# Audio.net
KiCad netlist of a schematic drawn in Altium Designer
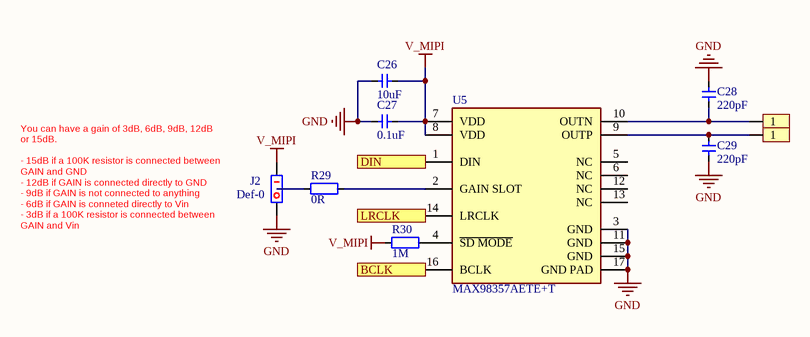
[diagram p0: Audio.SchDoc]

(export (version "E")
  (design (tool "Eeschema 10.0.6"))
  (components
    (comp (ref "*1") (value "SPEAKER") (footprint "SPEAKER") (libsource (lib "MyPcbLib") (part "SPEAKER")))
    (comp (ref "*2") (value "SPEAKER") (footprint "SPEAKER") (libsource (lib "MyPcbLib") (part "SPEAKER")))
    (comp (ref "C26")
      (value "10uF")
      (footprint "CAP_0402")
      (description "Capacitor")
      (libsource (lib "MyPcbLib") (part "电容-0402"))
    )
    (comp (ref "C27")
      (value "0.1uF")
      (footprint "CAP_0402")
      (description "Capacitor")
      (libsource (lib "MyPcbLib") (part "电容-0402"))
    )
    (comp (ref "C28")
      (value "220pF")
      (footprint "CAP_0402")
      (description "Capacitor")
      (libsource (lib "MyPcbLib") (part "电容-0402"))
    )
    (comp (ref "C29")
      (value "220pF")
      (footprint "CAP_0402")
      (description "Capacitor")
      (libsource (lib "MyPcbLib") (part "电容-0402"))
    )
    (comp (ref "J2")
      (value "Def-0")
      (footprint "jumper-3")
      (description "Resistor")
      (fields (field (name "PUBLISHER") "Altium Limited"))
      (libsource (lib "MyPcbLib") (part "选择跳线"))
    )
    (comp (ref "R29")
      (value "0R")
      (footprint "RES_0402")
      (description "Resistor")
      (libsource (lib "MyPcbLib") (part "电阻-0402"))
    )
    (comp (ref "R30")
      (value "1M")
      (footprint "RES_0402")
      (description "Resistor")
      (libsource (lib "MiniDisplay") (part "电阻-0402"))
    )
    (comp (ref "U5")
      (value "MAX98357AETE")
      (footprint "TQFN-16")
      (description "IC Amplifier IC 2-Channel (Stereo) Class D 16-TQFN (3x3)")
      (fields
        (field (name "MANUFACTURER") "Maxim Electronics")
        (field (name "MOUSER PART NUMBER") "700-MAX98357AETE+T")
        (field (name "PART NUMBER") "MAX98357AETE+T")
      )
      (libsource (lib "MiniDisplay") (part "MAX98357AETE"))
    )
  )
  (nets
    (net (code "1") (name "/BCLK") (class "Default")
      (node (ref "U5") (pin "16") (pinfunction "BCLK_16") (pintype "passive"))
    )
    (net (code "2") (name "/DIN") (class "Default")
      (node (ref "U5") (pin "1") (pinfunction "DIN_1") (pintype "passive"))
    )
    (net (code "3") (name "/LRCLK") (class "Default")
      (node (ref "U5") (pin "14") (pinfunction "LRCLK_14") (pintype "passive"))
    )
    (net (code "4") (name "GND") (class "Default")
      (node (ref "C26") (pin "1") (pinfunction "1_1") (pintype "passive"))
      (node (ref "C27") (pin "1") (pinfunction "1_1") (pintype "passive"))
      (node (ref "C28") (pin "2") (pinfunction "2_2") (pintype "passive"))
      (node (ref "C29") (pin "2") (pinfunction "2_2") (pintype "passive"))
      (node (ref "J2") (pin "1") (pinfunction "1_1") (pintype "passive"))
      (node (ref "U5") (pin "11") (pinfunction "GND_11") (pintype "passive"))
      (node (ref "U5") (pin "15") (pinfunction "GND_15") (pintype "passive"))
      (node (ref "U5") (pin "17") (pinfunction "GND_PAD_17") (pintype "passive"))
      (node (ref "U5") (pin "3") (pinfunction "GND_3") (pintype "passive"))
    )
    (net (code "5") (name "Net-(J2-Pad2)") (class "Default")
      (node (ref "J2") (pin "2") (pinfunction "2_2") (pintype "passive"))
      (node (ref "R29") (pin "1") (pinfunction "1_1") (pintype "passive"))
    )
    (net (code "6") (name "Net-(U5-GAIN_SLOT)") (class "Default")
      (node (ref "R29") (pin "2") (pinfunction "2_2") (pintype "passive"))
      (node (ref "U5") (pin "2") (pinfunction "GAIN_SLOT_2") (pintype "passive"))
    )
    (net (code "7") (name "Net-(U5-OUTN)") (class "Default")
      (node (ref "*1") (pin "1") (pinfunction "1_1") (pintype "passive"))
      (node (ref "C28") (pin "1") (pinfunction "1_1") (pintype "passive"))
      (node (ref "U5") (pin "10") (pinfunction "OUTN_10") (pintype "passive"))
    )
    (net (code "8") (name "Net-(U5-OUTP)") (class "Default")
      (node (ref "*2") (pin "1") (pinfunction "1_1") (pintype "passive"))
      (node (ref "C29") (pin "1") (pinfunction "1_1") (pintype "passive"))
      (node (ref "U5") (pin "9") (pinfunction "OUTP_9") (pintype "passive"))
    )
    (net (code "9") (name "Net-(U5-~{SD_MODE})") (class "Default")
      (node (ref "R30") (pin "2") (pinfunction "2_2") (pintype "passive"))
      (node (ref "U5") (pin "4") (pinfunction "~{SD_MODE}_4") (pintype "passive"))
    )
    (net (code "10") (name "V_MIPI") (class "Default")
      (node (ref "C26") (pin "2") (pinfunction "2_2") (pintype "passive"))
      (node (ref "C27") (pin "2") (pinfunction "2_2") (pintype "passive"))
      (node (ref "J2") (pin "3") (pinfunction "3_3") (pintype "passive"))
      (node (ref "R30") (pin "1") (pinfunction "1_1") (pintype "passive"))
      (node (ref "U5") (pin "7") (pinfunction "VDD_7") (pintype "passive"))
      (node (ref "U5") (pin "8") (pinfunction "VDD_8") (pintype "passive"))
    )
    (net (code "11") (name "unconnected-(U5-NC-Pad5)") (class "Default")
      (node (ref "U5") (pin "5") (pinfunction "NC_5") (pintype "passive"))
    )
    (net (code "12") (name "unconnected-(U5-NC-Pad6)") (class "Default")
      (node (ref "U5") (pin "6") (pinfunction "NC_6") (pintype "passive"))
    )
    (net (code "13") (name "unconnected-(U5-NC-Pad12)") (class "Default")
      (node (ref "U5") (pin "12") (pinfunction "NC_12") (pintype "passive"))
    )
    (net (code "14") (name "unconnected-(U5-NC-Pad13)") (class "Default")
      (node (ref "U5") (pin "13") (pinfunction "NC_13") (pintype "passive"))
    )
  )
)
